# circuit.net
KiCad netlist of a schematic drawn in EAGLE
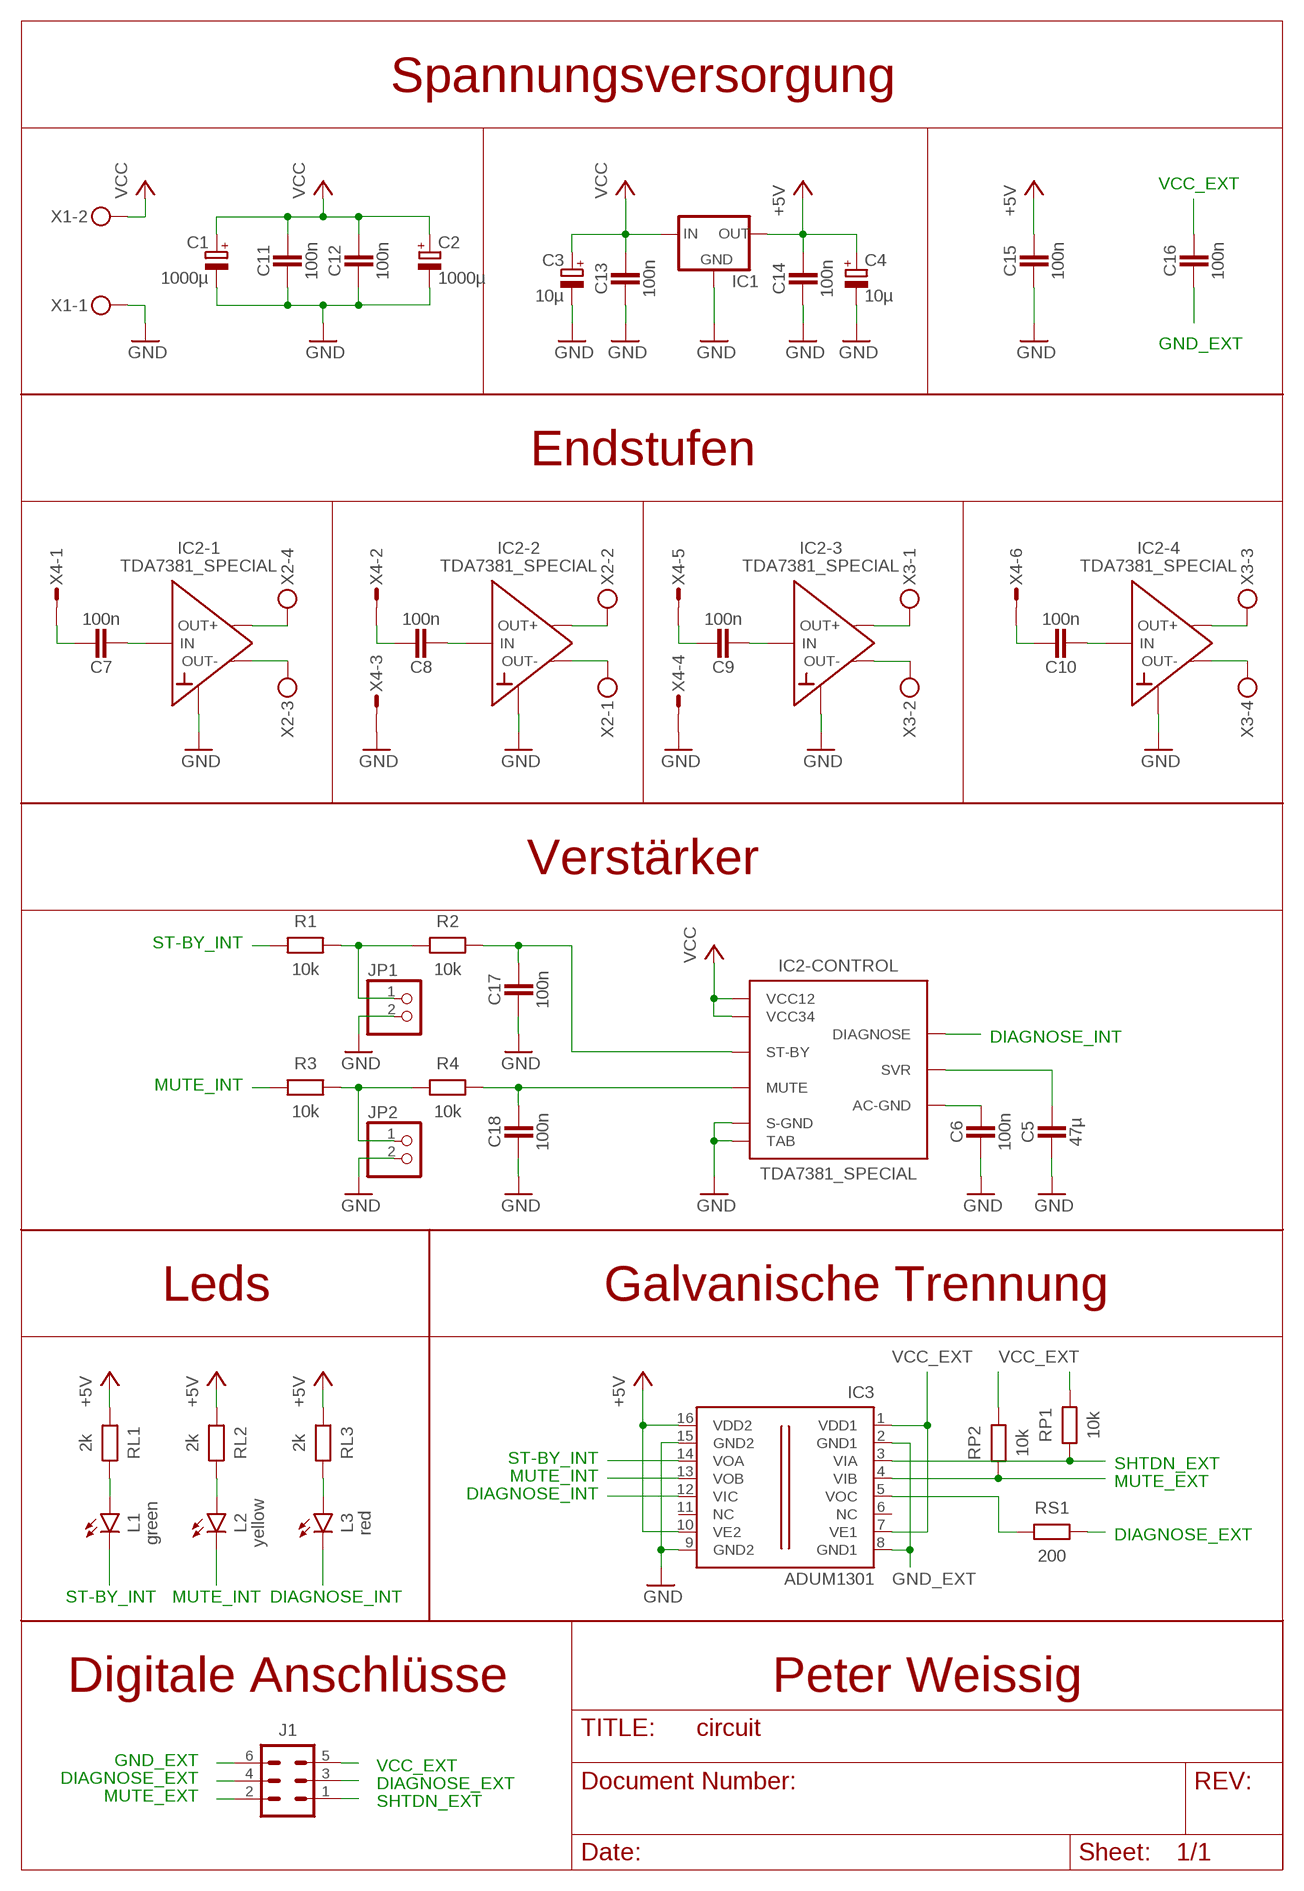
[diagram p0: schematic, sheet 1]

(export (version "E")
  (design (tool "Eeschema 10.0.6"))
  (components
    (comp (ref "C1")
      (value "1000µ")
      (footprint "eagle-import:E5-10,5")
      (libsource (lib "eagle-import") (part "CPOL-EUE5-10.5"))
    )
    (comp (ref "C2")
      (value "1000µ")
      (footprint "eagle-import:E5-10,5")
      (libsource (lib "eagle-import") (part "CPOL-EUE5-10.5"))
    )
    (comp (ref "C3")
      (value "10µ")
      (footprint "eagle-import:E2-5")
      (libsource (lib "eagle-import") (part "CPOL-EUE2-5"))
    )
    (comp (ref "C4")
      (value "10µ")
      (footprint "eagle-import:E2-5")
      (libsource (lib "eagle-import") (part "CPOL-EUE2-5"))
    )
    (comp (ref "C5")
      (value "47µ")
      (footprint "eagle-import:SMD_2312S")
      (libsource (lib "eagle-import") (part "CAPACITATOR-2312S"))
    )
    (comp (ref "C6")
      (value "100n")
      (footprint "eagle-import:SMD_1206")
      (libsource (lib "eagle-import") (part "CAPACITATOR-1206"))
    )
    (comp (ref "C7")
      (value "100n")
      (footprint "eagle-import:C_THT_3")
      (libsource (lib "eagle-import") (part "CAPACITATOR-5MM"))
    )
    (comp (ref "C8")
      (value "100n")
      (footprint "eagle-import:C_THT_3")
      (libsource (lib "eagle-import") (part "CAPACITATOR-5MM"))
    )
    (comp (ref "C9")
      (value "100n")
      (footprint "eagle-import:C_THT_3")
      (libsource (lib "eagle-import") (part "CAPACITATOR-5MM"))
    )
    (comp (ref "C10")
      (value "100n")
      (footprint "eagle-import:C_THT_3")
      (libsource (lib "eagle-import") (part "CAPACITATOR-5MM"))
    )
    (comp (ref "C11")
      (value "100n")
      (footprint "eagle-import:SMD_1206")
      (libsource (lib "eagle-import") (part "CAPACITATOR-1206"))
    )
    (comp (ref "C12")
      (value "100n")
      (footprint "eagle-import:SMD_1206")
      (libsource (lib "eagle-import") (part "CAPACITATOR-1206"))
    )
    (comp (ref "C13")
      (value "100n")
      (footprint "eagle-import:SMD_1206")
      (libsource (lib "eagle-import") (part "CAPACITATOR-1206"))
    )
    (comp (ref "C14")
      (value "100n")
      (footprint "eagle-import:SMD_1206")
      (libsource (lib "eagle-import") (part "CAPACITATOR-1206"))
    )
    (comp (ref "C15")
      (value "100n")
      (footprint "eagle-import:SMD_1206")
      (libsource (lib "eagle-import") (part "CAPACITATOR-1206"))
    )
    (comp (ref "C16")
      (value "100n")
      (footprint "eagle-import:SMD_1206")
      (libsource (lib "eagle-import") (part "CAPACITATOR-1206"))
    )
    (comp (ref "C17")
      (value "100n")
      (footprint "eagle-import:C_THT_3")
      (libsource (lib "eagle-import") (part "CAPACITATOR-5MM"))
    )
    (comp (ref "C18")
      (value "100n")
      (footprint "eagle-import:C_THT_3")
      (libsource (lib "eagle-import") (part "CAPACITATOR-5MM"))
    )
    (comp (ref "IC1")
      (value "78XXS")
      (footprint "eagle-import:78XXS")
      (libsource (lib "eagle-import") (part "78XXS"))
    )
    (comp (ref "IC2")
      (value "TDA7381_SPECIAL")
      (footprint "eagle-import:IC_FLEXIWATT25_SPECIAL")
      (libsource (lib "eagle-import") (part "TDA7381_SPECIAL"))
    )
    (comp (ref "IC3")
      (value "ADUM1301")
      (footprint "eagle-import:SO-16W")
      (fields (field (name "MPN") "ADUM1301BRWZ"))
      (libsource (lib "eagle-import") (part "ADUM1301"))
    )
    (comp (ref "J1")
      (value "STECKER_WANNE_6")
      (footprint "eagle-import:STECKER_WANNE_6")
      (libsource (lib "eagle-import") (part "STECKER_WANNE_6"))
    )
    (comp (ref "JP1")
      (value "PINHD-1X2")
      (footprint "eagle-import:1X02")
      (libsource (lib "eagle-import") (part "PINHD-1X2"))
    )
    (comp (ref "JP2")
      (value "PINHD-1X2")
      (footprint "eagle-import:1X02")
      (libsource (lib "eagle-import") (part "PINHD-1X2"))
    )
    (comp (ref "L1")
      (value "green")
      (footprint "eagle-import:LED_3MM")
      (libsource (lib "eagle-import") (part "LED-3MM"))
    )
    (comp (ref "L2")
      (value "yellow")
      (footprint "eagle-import:LED_3MM")
      (libsource (lib "eagle-import") (part "LED-3MM"))
    )
    (comp (ref "L3")
      (value "red")
      (footprint "eagle-import:LED_3MM")
      (libsource (lib "eagle-import") (part "LED-3MM"))
    )
    (comp (ref "R1")
      (value "10k")
      (footprint "eagle-import:SMD_1206")
      (libsource (lib "eagle-import") (part "RESISTOR-1206"))
    )
    (comp (ref "R2")
      (value "10k")
      (footprint "eagle-import:SMD_1206")
      (libsource (lib "eagle-import") (part "RESISTOR-1206"))
    )
    (comp (ref "R3")
      (value "10k")
      (footprint "eagle-import:SMD_1206")
      (libsource (lib "eagle-import") (part "RESISTOR-1206"))
    )
    (comp (ref "R4")
      (value "10k")
      (footprint "eagle-import:SMD_1206")
      (libsource (lib "eagle-import") (part "RESISTOR-1206"))
    )
    (comp (ref "RL1")
      (value "2k")
      (footprint "eagle-import:SMD_1206")
      (libsource (lib "eagle-import") (part "RESISTOR-1206"))
    )
    (comp (ref "RL2")
      (value "2k")
      (footprint "eagle-import:SMD_1206")
      (libsource (lib "eagle-import") (part "RESISTOR-1206"))
    )
    (comp (ref "RL3")
      (value "2k")
      (footprint "eagle-import:SMD_1206")
      (libsource (lib "eagle-import") (part "RESISTOR-1206"))
    )
    (comp (ref "RP1")
      (value "10k")
      (footprint "eagle-import:SMD_1206")
      (libsource (lib "eagle-import") (part "RESISTOR-1206"))
    )
    (comp (ref "RP2")
      (value "10k")
      (footprint "eagle-import:SMD_1206")
      (libsource (lib "eagle-import") (part "RESISTOR-1206"))
    )
    (comp (ref "RS1")
      (value "200")
      (footprint "eagle-import:SMD_1206")
      (libsource (lib "eagle-import") (part "RESISTOR-1206"))
    )
    (comp (ref "X1")
      (value "STECKER_SPG_2")
      (footprint "eagle-import:STECKER_SPG_2")
      (libsource (lib "eagle-import") (part "STECKER_SPG_2"))
    )
    (comp (ref "X2")
      (value "STECKER_SPG_4")
      (footprint "eagle-import:STECKER_SPG_4")
      (libsource (lib "eagle-import") (part "STECKER_SPG_4"))
    )
    (comp (ref "X3")
      (value "STECKER_SPG_4")
      (footprint "eagle-import:STECKER_SPG_4")
      (libsource (lib "eagle-import") (part "STECKER_SPG_4"))
    )
    (comp (ref "X4")
      (value "STECKER_MICROMATCH_6")
      (footprint "eagle-import:STECKER_MICROMATCH_6")
      (libsource (lib "eagle-import") (part "STECKER_MICROMATCH_6"))
    )
  )
  (nets
    (net (code "1") (name "+5V") (class "Default")
      (node (ref "C14") (pin "1") (pinfunction "1_1") (pintype "passive"))
      (node (ref "C15") (pin "1") (pinfunction "1_1") (pintype "passive"))
      (node (ref "C4") (pin "+") (pinfunction "+_+") (pintype "passive"))
      (node (ref "IC1") (pin "OUT") (pinfunction "OUT_OUT") (pintype "passive"))
      (node (ref "IC3") (pin "10") (pinfunction "VE2_10") (pintype "input"))
      (node (ref "IC3") (pin "16") (pinfunction "VDD2_16") (pintype "input"))
      (node (ref "RL1") (pin "2") (pinfunction "P2_2") (pintype "passive"))
      (node (ref "RL2") (pin "2") (pinfunction "P2_2") (pintype "passive"))
      (node (ref "RL3") (pin "2") (pinfunction "P2_2") (pintype "passive"))
    )
    (net (code "2") (name "/DIAGNOSE_EXT") (class "Default")
      (node (ref "J1") (pin "3") (pinfunction "3_3") (pintype "passive"))
      (node (ref "J1") (pin "4") (pinfunction "4_4") (pintype "passive"))
      (node (ref "RS1") (pin "2") (pinfunction "P2_2") (pintype "passive"))
    )
    (net (code "3") (name "/DIAGNOSE_INT") (class "Default")
      (node (ref "IC2") (pin "25") (pinfunction "DIAGNOSE_25") (pintype "open_collector"))
      (node (ref "IC3") (pin "12") (pinfunction "VIC_12") (pintype "input"))
      (node (ref "L3") (pin "K") (pinfunction "C_K") (pintype "passive"))
    )
    (net (code "4") (name "/GND_EXT") (class "Default")
      (node (ref "C16") (pin "2") (pinfunction "2_2") (pintype "passive"))
      (node (ref "IC3") (pin "2") (pinfunction "GND1_2") (pintype "input"))
      (node (ref "IC3") (pin "8") (pinfunction "GND1_8") (pintype "input"))
      (node (ref "J1") (pin "6") (pinfunction "6_6") (pintype "passive"))
    )
    (net (code "5") (name "/MUTE_EXT") (class "Default")
      (node (ref "IC3") (pin "4") (pinfunction "VIB_4") (pintype "input"))
      (node (ref "J1") (pin "2") (pinfunction "2_2") (pintype "passive"))
      (node (ref "RP2") (pin "1") (pinfunction "P1_1") (pintype "passive"))
    )
    (net (code "6") (name "/MUTE_INT") (class "Default")
      (node (ref "IC3") (pin "13") (pinfunction "VOB_13") (pintype "tri_state"))
      (node (ref "L2") (pin "K") (pinfunction "C_K") (pintype "passive"))
      (node (ref "R3") (pin "1") (pinfunction "P1_1") (pintype "passive"))
    )
    (net (code "7") (name "/SHTDN_EXT") (class "Default")
      (node (ref "IC3") (pin "3") (pinfunction "VIA_3") (pintype "input"))
      (node (ref "J1") (pin "1") (pinfunction "1_1") (pintype "passive"))
      (node (ref "RP1") (pin "1") (pinfunction "P1_1") (pintype "passive"))
    )
    (net (code "8") (name "/ST-BY_INT") (class "Default")
      (node (ref "IC3") (pin "14") (pinfunction "VOA_14") (pintype "tri_state"))
      (node (ref "L1") (pin "K") (pinfunction "C_K") (pintype "passive"))
      (node (ref "R1") (pin "1") (pinfunction "P1_1") (pintype "passive"))
    )
    (net (code "9") (name "/VCC_EXT") (class "Default")
      (node (ref "C16") (pin "1") (pinfunction "1_1") (pintype "passive"))
      (node (ref "IC3") (pin "1") (pinfunction "VDD1_1") (pintype "input"))
      (node (ref "IC3") (pin "7") (pinfunction "VE1_7") (pintype "input"))
      (node (ref "J1") (pin "5") (pinfunction "5_5") (pintype "passive"))
      (node (ref "RP1") (pin "2") (pinfunction "P2_2") (pintype "passive"))
      (node (ref "RP2") (pin "2") (pinfunction "P2_2") (pintype "passive"))
    )
    (net (code "10") (name "GND") (class "Default")
      (node (ref "C1") (pin "-") (pinfunction "-_-") (pintype "passive"))
      (node (ref "C11") (pin "2") (pinfunction "2_2") (pintype "passive"))
      (node (ref "C12") (pin "2") (pinfunction "2_2") (pintype "passive"))
      (node (ref "C13") (pin "2") (pinfunction "2_2") (pintype "passive"))
      (node (ref "C14") (pin "2") (pinfunction "2_2") (pintype "passive"))
      (node (ref "C15") (pin "2") (pinfunction "2_2") (pintype "passive"))
      (node (ref "C17") (pin "1") (pinfunction "1_1") (pintype "passive"))
      (node (ref "C18") (pin "1") (pinfunction "1_1") (pintype "passive"))
      (node (ref "C2") (pin "-") (pinfunction "-_-") (pintype "passive"))
      (node (ref "C3") (pin "-") (pinfunction "-_-") (pintype "passive"))
      (node (ref "C4") (pin "-") (pinfunction "-_-") (pintype "passive"))
      (node (ref "C5") (pin "2") (pinfunction "2_2") (pintype "passive"))
      (node (ref "C6") (pin "2") (pinfunction "2_2") (pintype "passive"))
      (node (ref "IC1") (pin "GND") (pinfunction "GND_GND") (pintype "input"))
      (node (ref "IC2") (pin "1") (pinfunction "TAB_1") (pintype "input"))
      (node (ref "IC2") (pin "13") (pinfunction "S-GND_13") (pintype "input"))
      (node (ref "IC2") (pin "18") (pinfunction "GND_18") (pintype "power_in"))
      (node (ref "IC2") (pin "2") (pinfunction "GND_2") (pintype "power_in"))
      (node (ref "IC2") (pin "24") (pinfunction "GND_24") (pintype "power_in"))
      (node (ref "IC2") (pin "8") (pinfunction "GND_8") (pintype "power_in"))
      (node (ref "IC3") (pin "15") (pinfunction "GND2_15") (pintype "input"))
      (node (ref "IC3") (pin "9") (pinfunction "GND2_9") (pintype "input"))
      (node (ref "JP1") (pin "2") (pinfunction "2_2") (pintype "passive"))
      (node (ref "JP2") (pin "2") (pinfunction "2_2") (pintype "passive"))
      (node (ref "X1") (pin "1") (pinfunction "KL_1") (pintype "passive"))
      (node (ref "X4") (pin "3") (pinfunction "S_3") (pintype "passive"))
      (node (ref "X4") (pin "4") (pinfunction "S_4") (pintype "passive"))
    )
    (net (code "11") (name "Net-(IC2A-IN)") (class "Default")
      (node (ref "C7") (pin "2") (pinfunction "2_2") (pintype "passive"))
      (node (ref "IC2") (pin "11") (pinfunction "IN_11") (pintype "input"))
    )
    (net (code "12") (name "Net-(IC2A-OUT+)") (class "Default")
      (node (ref "IC2") (pin "9") (pinfunction "OUT+_9") (pintype "output"))
      (node (ref "X2") (pin "4") (pinfunction "KL_4") (pintype "passive"))
    )
    (net (code "13") (name "Net-(IC2A-OUT-)") (class "Default")
      (node (ref "IC2") (pin "7") (pinfunction "OUT-_7") (pintype "output"))
      (node (ref "X2") (pin "3") (pinfunction "KL_3") (pintype "passive"))
    )
    (net (code "14") (name "Net-(IC2B-IN)") (class "Default")
      (node (ref "C8") (pin "2") (pinfunction "2_2") (pintype "passive"))
      (node (ref "IC2") (pin "12") (pinfunction "IN_12") (pintype "input"))
    )
    (net (code "15") (name "Net-(IC2B-OUT+)") (class "Default")
      (node (ref "IC2") (pin "5") (pinfunction "OUT+_5") (pintype "output"))
      (node (ref "X2") (pin "2") (pinfunction "KL_2") (pintype "passive"))
    )
    (net (code "16") (name "Net-(IC2B-OUT-)") (class "Default")
      (node (ref "IC2") (pin "3") (pinfunction "OUT-_3") (pintype "output"))
      (node (ref "X2") (pin "1") (pinfunction "KL_1") (pintype "passive"))
    )
    (net (code "17") (name "Net-(IC2C-IN)") (class "Default")
      (node (ref "C9") (pin "2") (pinfunction "2_2") (pintype "passive"))
      (node (ref "IC2") (pin "15") (pinfunction "IN_15") (pintype "input"))
    )
    (net (code "18") (name "Net-(IC2C-OUT+)") (class "Default")
      (node (ref "IC2") (pin "17") (pinfunction "OUT+_17") (pintype "output"))
      (node (ref "X3") (pin "1") (pinfunction "KL_1") (pintype "passive"))
    )
    (net (code "19") (name "Net-(IC2C-OUT-)") (class "Default")
      (node (ref "IC2") (pin "19") (pinfunction "OUT-_19") (pintype "output"))
      (node (ref "X3") (pin "2") (pinfunction "KL_2") (pintype "passive"))
    )
    (net (code "20") (name "Net-(IC2D-IN)") (class "Default")
      (node (ref "C10") (pin "2") (pinfunction "2_2") (pintype "passive"))
      (node (ref "IC2") (pin "14") (pinfunction "IN_14") (pintype "input"))
    )
    (net (code "21") (name "Net-(IC2D-OUT+)") (class "Default")
      (node (ref "IC2") (pin "21") (pinfunction "OUT+_21") (pintype "output"))
      (node (ref "X3") (pin "3") (pinfunction "KL_3") (pintype "passive"))
    )
    (net (code "22") (name "Net-(IC2D-OUT-)") (class "Default")
      (node (ref "IC2") (pin "23") (pinfunction "OUT-_23") (pintype "output"))
      (node (ref "X3") (pin "4") (pinfunction "KL_4") (pintype "passive"))
    )
    (net (code "23") (name "Net-(IC2E-AC-GND)") (class "Default")
      (node (ref "C6") (pin "1") (pinfunction "1_1") (pintype "passive"))
      (node (ref "IC2") (pin "16") (pinfunction "AC-GND_16") (pintype "power_in"))
    )
    (net (code "24") (name "Net-(IC2E-MUTE)") (class "Default")
      (node (ref "C18") (pin "2") (pinfunction "2_2") (pintype "passive"))
      (node (ref "IC2") (pin "22") (pinfunction "MUTE_22") (pintype "input"))
      (node (ref "R4") (pin "2") (pinfunction "P2_2") (pintype "passive"))
    )
    (net (code "25") (name "Net-(IC2E-ST-BY)") (class "Default")
      (node (ref "C17") (pin "2") (pinfunction "2_2") (pintype "passive"))
      (node (ref "IC2") (pin "4") (pinfunction "ST-BY_4") (pintype "input"))
      (node (ref "R2") (pin "2") (pinfunction "P2_2") (pintype "passive"))
    )
    (net (code "26") (name "Net-(IC2E-SVR)") (class "Default")
      (node (ref "C5") (pin "1") (pinfunction "1_1") (pintype "passive"))
      (node (ref "IC2") (pin "10") (pinfunction "SVR_10") (pintype "power_in"))
    )
    (net (code "27") (name "Net-(IC3-VOC)") (class "Default")
      (node (ref "IC3") (pin "5") (pinfunction "VOC_5") (pintype "tri_state"))
      (node (ref "RS1") (pin "1") (pinfunction "P1_1") (pintype "passive"))
    )
    (net (code "28") (name "Net-(R1-P2)") (class "Default")
      (node (ref "JP1") (pin "1") (pinfunction "1_1") (pintype "passive"))
      (node (ref "R1") (pin "2") (pinfunction "P2_2") (pintype "passive"))
      (node (ref "R2") (pin "1") (pinfunction "P1_1") (pintype "passive"))
    )
    (net (code "29") (name "Net-(R3-P2)") (class "Default")
      (node (ref "JP2") (pin "1") (pinfunction "1_1") (pintype "passive"))
      (node (ref "R3") (pin "2") (pinfunction "P2_2") (pintype "passive"))
      (node (ref "R4") (pin "1") (pinfunction "P1_1") (pintype "passive"))
    )
    (net (code "30") (name "Net-(RL1-P1)") (class "Default")
      (node (ref "L1") (pin "A") (pinfunction "A_A") (pintype "passive"))
      (node (ref "RL1") (pin "1") (pinfunction "P1_1") (pintype "passive"))
    )
    (net (code "31") (name "Net-(RL2-P1)") (class "Default")
      (node (ref "L2") (pin "A") (pinfunction "A_A") (pintype "passive"))
      (node (ref "RL2") (pin "1") (pinfunction "P1_1") (pintype "passive"))
    )
    (net (code "32") (name "Net-(RL3-P1)") (class "Default")
      (node (ref "L3") (pin "A") (pinfunction "A_A") (pintype "passive"))
      (node (ref "RL3") (pin "1") (pinfunction "P1_1") (pintype "passive"))
    )
    (net (code "33") (name "Net-(X4A-S)") (class "Default")
      (node (ref "C7") (pin "1") (pinfunction "1_1") (pintype "passive"))
      (node (ref "X4") (pin "1") (pinfunction "S_1") (pintype "passive"))
    )
    (net (code "34") (name "Net-(X4B-S)") (class "Default")
      (node (ref "C8") (pin "1") (pinfunction "1_1") (pintype "passive"))
      (node (ref "X4") (pin "2") (pinfunction "S_2") (pintype "passive"))
    )
    (net (code "35") (name "Net-(X4E-S)") (class "Default")
      (node (ref "C9") (pin "1") (pinfunction "1_1") (pintype "passive"))
      (node (ref "X4") (pin "5") (pinfunction "S_5") (pintype "passive"))
    )
    (net (code "36") (name "Net-(X4F-S)") (class "Default")
      (node (ref "C10") (pin "1") (pinfunction "1_1") (pintype "passive"))
      (node (ref "X4") (pin "6") (pinfunction "S_6") (pintype "passive"))
    )
    (net (code "37") (name "VCC") (class "Default")
      (node (ref "C1") (pin "+") (pinfunction "+_+") (pintype "passive"))
      (node (ref "C11") (pin "1") (pinfunction "1_1") (pintype "passive"))
      (node (ref "C12") (pin "1") (pinfunction "1_1") (pintype "passive"))
      (node (ref "C13") (pin "1") (pinfunction "1_1") (pintype "passive"))
      (node (ref "C2") (pin "+") (pinfunction "+_+") (pintype "passive"))
      (node (ref "C3") (pin "+") (pinfunction "+_+") (pintype "passive"))
      (node (ref "IC1") (pin "IN") (pinfunction "IN_IN") (pintype "input"))
      (node (ref "IC2") (pin "20") (pinfunction "VCC34_20") (pintype "input"))
      (node (ref "IC2") (pin "6") (pinfunction "VCC12_6") (pintype "input"))
      (node (ref "X1") (pin "2") (pinfunction "KL_2") (pintype "passive"))
    )
    (net (code "38") (name "unconnected-(IC3-NC-Pad6)") (class "Default")
      (node (ref "IC3") (pin "6") (pinfunction "NC_6") (pintype "no_connect"))
    )
    (net (code "39") (name "unconnected-(IC3-NC-Pad11)") (class "Default")
      (node (ref "IC3") (pin "11") (pinfunction "NC_11") (pintype "no_connect"))
    )
  )
)
